# Encoder_pHAT.net
KiCad netlist of a schematic drawn in EAGLE
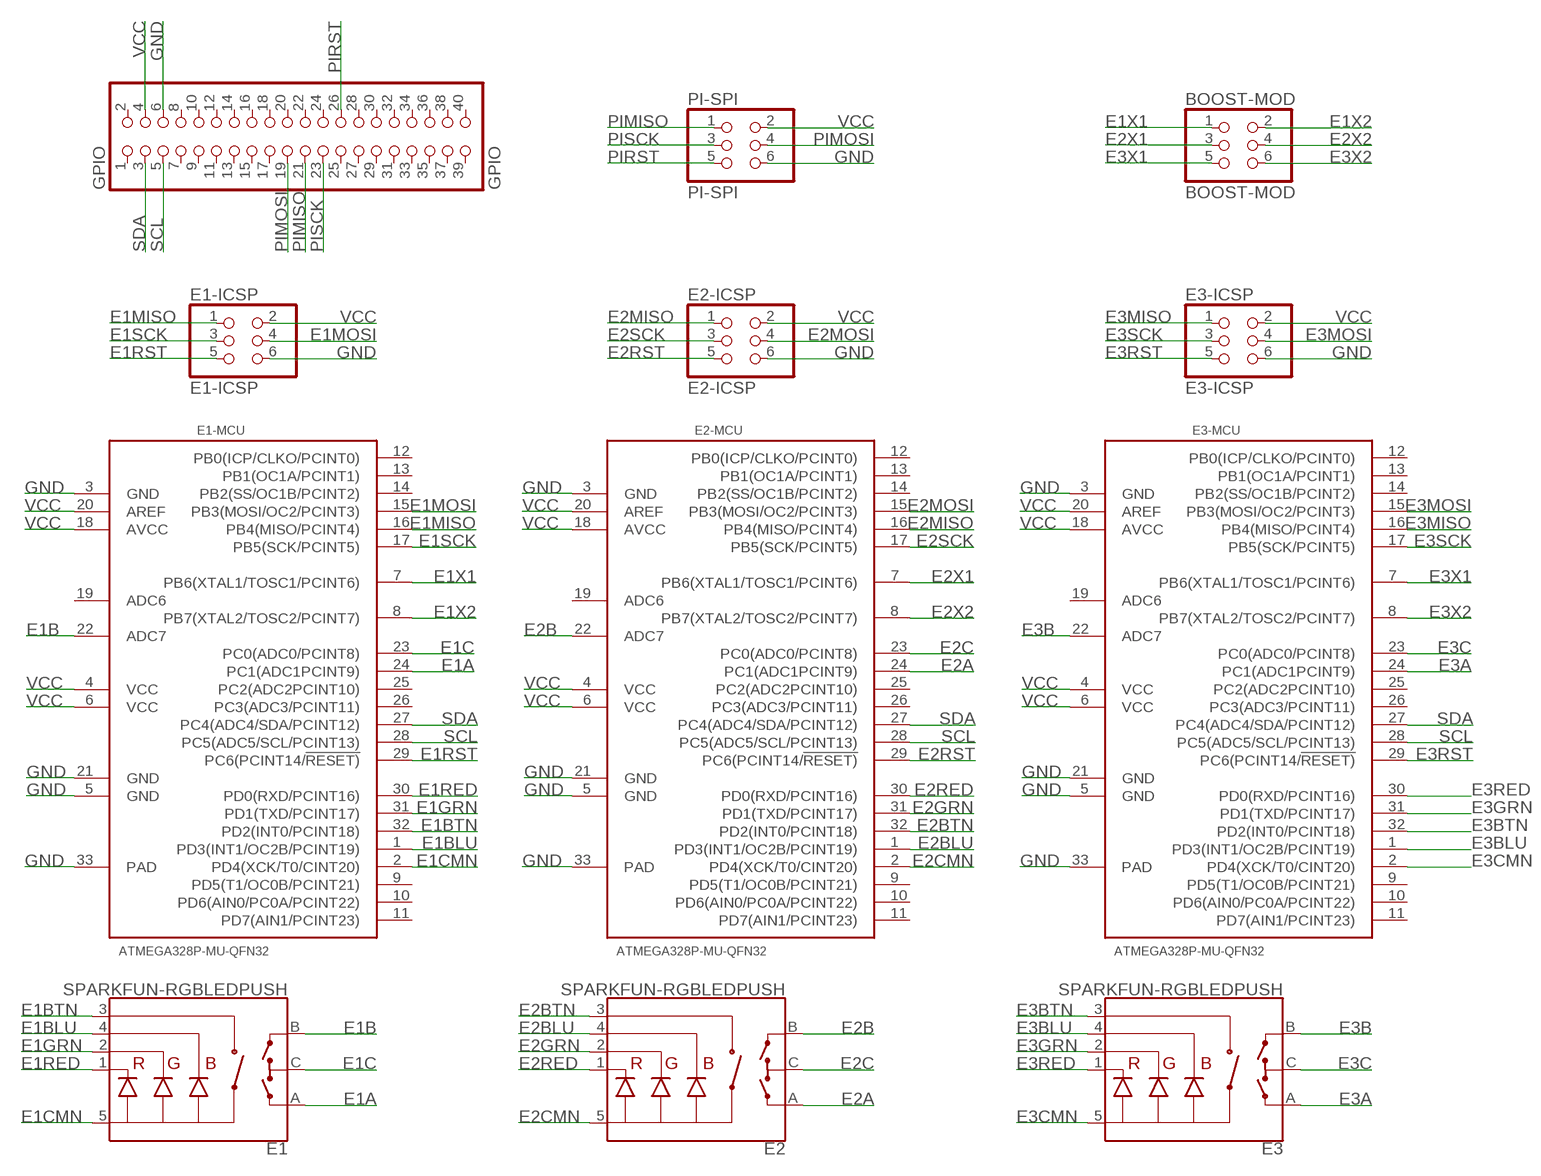
[diagram p0: schematic, sheet 1]

(export (version "E")
  (design (tool "Eeschema 10.0.6"))
  (components
    (comp (ref "BOOST-MOD")
      (value "BOOST-MOD")
      (footprint "eagle-import:2X03")
      (libsource (lib "eagle-import") (part "PINHD-2X3"))
    )
    (comp (ref "E1")
      (value "SPARKFUN-RGBLEDPUSH")
      (footprint "eagle-import:ENCODER_LED_3")
      (libsource (lib "eagle-import") (part "ENCODER-RGB-SWITCH"))
    )
    (comp (ref "E1-ICSP")
      (value "E1-ICSP")
      (footprint "eagle-import:2X03")
      (libsource (lib "eagle-import") (part "PINHD-2X3"))
    )
    (comp (ref "E1-MCU")
      (value "ATMEGA328P-MU-QFN32")
      (footprint "eagle-import:QFN32G-0.5-5X5MM")
      (fields (field (name "MPN") "ATMEGA328P-MU"))
      (libsource (lib "eagle-import") (part "MCU-ATMEGA328P-MU(QFN32)"))
    )
    (comp (ref "E2")
      (value "SPARKFUN-RGBLEDPUSH")
      (footprint "eagle-import:ENCODER_LED_3")
      (libsource (lib "eagle-import") (part "ENCODER-RGB-SWITCH"))
    )
    (comp (ref "E2-ICSP")
      (value "E2-ICSP")
      (footprint "eagle-import:2X03")
      (libsource (lib "eagle-import") (part "PINHD-2X3"))
    )
    (comp (ref "E2-MCU")
      (value "ATMEGA328P-MU-QFN32")
      (footprint "eagle-import:QFN32G-0.5-5X5MM")
      (fields (field (name "MPN") "ATMEGA328P-MU"))
      (libsource (lib "eagle-import") (part "MCU-ATMEGA328P-MU(QFN32)"))
    )
    (comp (ref "E3")
      (value "SPARKFUN-RGBLEDPUSH")
      (footprint "eagle-import:ENCODER_LED_3")
      (libsource (lib "eagle-import") (part "ENCODER-RGB-SWITCH"))
    )
    (comp (ref "E3-ICSP")
      (value "E3-ICSP")
      (footprint "eagle-import:2X03")
      (libsource (lib "eagle-import") (part "PINHD-2X3"))
    )
    (comp (ref "E3-MCU")
      (value "ATMEGA328P-MU-QFN32")
      (footprint "eagle-import:QFN32G-0.5-5X5MM")
      (fields (field (name "MPN") "ATMEGA328P-MU"))
      (libsource (lib "eagle-import") (part "MCU-ATMEGA328P-MU(QFN32)"))
    )
    (comp (ref "GPIO")
      (value "GPIO")
      (footprint "eagle-import:2X20")
      (libsource (lib "eagle-import") (part "PINHD-2X20"))
    )
    (comp (ref "PI-SPI")
      (value "PI-SPI")
      (footprint "eagle-import:2X03")
      (libsource (lib "eagle-import") (part "PINHD-2X3"))
    )
  )
  (nets
    (net (code "1") (name "/E1A") (class "Default")
      (node (ref "E1") (pin "A") (pinfunction "A_A") (pintype "bidirectional"))
      (node (ref "E1-MCU") (pin "24") (pinfunction "PC1(ADC1PCINT9)_24") (pintype "bidirectional"))
    )
    (net (code "2") (name "/E1B") (class "Default")
      (node (ref "E1") (pin "B") (pinfunction "B_B") (pintype "bidirectional"))
      (node (ref "E1-MCU") (pin "22") (pinfunction "ADC7_22") (pintype "bidirectional"))
    )
    (net (code "3") (name "/E1BLU") (class "Default")
      (node (ref "E1") (pin "4") (pinfunction "-B_4") (pintype "passive"))
      (node (ref "E1-MCU") (pin "1") (pinfunction "PD3(INT1/OC2B/PCINT19)_1") (pintype "bidirectional"))
    )
    (net (code "4") (name "/E1BTN") (class "Default")
      (node (ref "E1") (pin "3") (pinfunction "SW_3") (pintype "passive"))
      (node (ref "E1-MCU") (pin "32") (pinfunction "PD2(INT0/PCINT18)_32") (pintype "bidirectional"))
    )
    (net (code "5") (name "/E1C") (class "Default")
      (node (ref "E1") (pin "C") (pinfunction "C_C") (pintype "bidirectional"))
      (node (ref "E1-MCU") (pin "23") (pinfunction "PC0(ADC0/PCINT8)_23") (pintype "bidirectional"))
    )
    (net (code "6") (name "/E1CMN") (class "Default")
      (node (ref "E1") (pin "5") (pinfunction "+_5") (pintype "passive"))
      (node (ref "E1-MCU") (pin "2") (pinfunction "PD4(XCK/T0/CINT20)_2") (pintype "bidirectional"))
    )
    (net (code "7") (name "/E1GRN") (class "Default")
      (node (ref "E1") (pin "2") (pinfunction "-G_2") (pintype "passive"))
      (node (ref "E1-MCU") (pin "31") (pinfunction "PD1(TXD/PCINT17)_31") (pintype "bidirectional"))
    )
    (net (code "8") (name "/E1MISO") (class "Default")
      (node (ref "E1-ICSP") (pin "1") (pinfunction "1_1") (pintype "passive"))
      (node (ref "E1-MCU") (pin "16") (pinfunction "PB4(MISO/PCINT4)_16") (pintype "bidirectional"))
    )
    (net (code "9") (name "/E1MOSI") (class "Default")
      (node (ref "E1-ICSP") (pin "4") (pinfunction "4_4") (pintype "passive"))
      (node (ref "E1-MCU") (pin "15") (pinfunction "PB3(MOSI/OC2/PCINT3)_15") (pintype "bidirectional"))
    )
    (net (code "10") (name "/E1RED") (class "Default")
      (node (ref "E1") (pin "1") (pinfunction "-R_1") (pintype "passive"))
      (node (ref "E1-MCU") (pin "30") (pinfunction "PD0(RXD/PCINT16)_30") (pintype "bidirectional"))
    )
    (net (code "11") (name "/E1RST") (class "Default")
      (node (ref "E1-ICSP") (pin "5") (pinfunction "5_5") (pintype "passive"))
      (node (ref "E1-MCU") (pin "29") (pinfunction "PC6(PCINT14/~{RESET})_29") (pintype "bidirectional"))
    )
    (net (code "12") (name "/E1SCK") (class "Default")
      (node (ref "E1-ICSP") (pin "3") (pinfunction "3_3") (pintype "passive"))
      (node (ref "E1-MCU") (pin "17") (pinfunction "PB5(SCK/PCINT5)_17") (pintype "bidirectional"))
    )
    (net (code "13") (name "/E1X1") (class "Default")
      (node (ref "BOOST-MOD") (pin "1") (pinfunction "1_1") (pintype "passive"))
      (node (ref "E1-MCU") (pin "7") (pinfunction "PB6(XTAL1/TOSC1/PCINT6)_7") (pintype "bidirectional"))
    )
    (net (code "14") (name "/E1X2") (class "Default")
      (node (ref "BOOST-MOD") (pin "2") (pinfunction "2_2") (pintype "passive"))
      (node (ref "E1-MCU") (pin "8") (pinfunction "PB7(XTAL2/TOSC2/PCINT7)_8") (pintype "bidirectional"))
    )
    (net (code "15") (name "/E2A") (class "Default")
      (node (ref "E2") (pin "A") (pinfunction "A_A") (pintype "bidirectional"))
      (node (ref "E2-MCU") (pin "24") (pinfunction "PC1(ADC1PCINT9)_24") (pintype "bidirectional"))
    )
    (net (code "16") (name "/E2B") (class "Default")
      (node (ref "E2") (pin "B") (pinfunction "B_B") (pintype "bidirectional"))
      (node (ref "E2-MCU") (pin "22") (pinfunction "ADC7_22") (pintype "bidirectional"))
    )
    (net (code "17") (name "/E2BLU") (class "Default")
      (node (ref "E2") (pin "4") (pinfunction "-B_4") (pintype "passive"))
      (node (ref "E2-MCU") (pin "1") (pinfunction "PD3(INT1/OC2B/PCINT19)_1") (pintype "bidirectional"))
    )
    (net (code "18") (name "/E2BTN") (class "Default")
      (node (ref "E2") (pin "3") (pinfunction "SW_3") (pintype "passive"))
      (node (ref "E2-MCU") (pin "32") (pinfunction "PD2(INT0/PCINT18)_32") (pintype "bidirectional"))
    )
    (net (code "19") (name "/E2C") (class "Default")
      (node (ref "E2") (pin "C") (pinfunction "C_C") (pintype "bidirectional"))
      (node (ref "E2-MCU") (pin "23") (pinfunction "PC0(ADC0/PCINT8)_23") (pintype "bidirectional"))
    )
    (net (code "20") (name "/E2CMN") (class "Default")
      (node (ref "E2") (pin "5") (pinfunction "+_5") (pintype "passive"))
      (node (ref "E2-MCU") (pin "2") (pinfunction "PD4(XCK/T0/CINT20)_2") (pintype "bidirectional"))
    )
    (net (code "21") (name "/E2GRN") (class "Default")
      (node (ref "E2") (pin "2") (pinfunction "-G_2") (pintype "passive"))
      (node (ref "E2-MCU") (pin "31") (pinfunction "PD1(TXD/PCINT17)_31") (pintype "bidirectional"))
    )
    (net (code "22") (name "/E2MISO") (class "Default")
      (node (ref "E2-ICSP") (pin "1") (pinfunction "1_1") (pintype "passive"))
      (node (ref "E2-MCU") (pin "16") (pinfunction "PB4(MISO/PCINT4)_16") (pintype "bidirectional"))
    )
    (net (code "23") (name "/E2MOSI") (class "Default")
      (node (ref "E2-ICSP") (pin "4") (pinfunction "4_4") (pintype "passive"))
      (node (ref "E2-MCU") (pin "15") (pinfunction "PB3(MOSI/OC2/PCINT3)_15") (pintype "bidirectional"))
    )
    (net (code "24") (name "/E2RED") (class "Default")
      (node (ref "E2") (pin "1") (pinfunction "-R_1") (pintype "passive"))
      (node (ref "E2-MCU") (pin "30") (pinfunction "PD0(RXD/PCINT16)_30") (pintype "bidirectional"))
    )
    (net (code "25") (name "/E2RST") (class "Default")
      (node (ref "E2-ICSP") (pin "5") (pinfunction "5_5") (pintype "passive"))
      (node (ref "E2-MCU") (pin "29") (pinfunction "PC6(PCINT14/~{RESET})_29") (pintype "bidirectional"))
    )
    (net (code "26") (name "/E2SCK") (class "Default")
      (node (ref "E2-ICSP") (pin "3") (pinfunction "3_3") (pintype "passive"))
      (node (ref "E2-MCU") (pin "17") (pinfunction "PB5(SCK/PCINT5)_17") (pintype "bidirectional"))
    )
    (net (code "27") (name "/E2X1") (class "Default")
      (node (ref "BOOST-MOD") (pin "3") (pinfunction "3_3") (pintype "passive"))
      (node (ref "E2-MCU") (pin "7") (pinfunction "PB6(XTAL1/TOSC1/PCINT6)_7") (pintype "bidirectional"))
    )
    (net (code "28") (name "/E2X2") (class "Default")
      (node (ref "BOOST-MOD") (pin "4") (pinfunction "4_4") (pintype "passive"))
      (node (ref "E2-MCU") (pin "8") (pinfunction "PB7(XTAL2/TOSC2/PCINT7)_8") (pintype "bidirectional"))
    )
    (net (code "29") (name "/E3A") (class "Default")
      (node (ref "E3") (pin "A") (pinfunction "A_A") (pintype "bidirectional"))
      (node (ref "E3-MCU") (pin "24") (pinfunction "PC1(ADC1PCINT9)_24") (pintype "bidirectional"))
    )
    (net (code "30") (name "/E3B") (class "Default")
      (node (ref "E3") (pin "B") (pinfunction "B_B") (pintype "bidirectional"))
      (node (ref "E3-MCU") (pin "22") (pinfunction "ADC7_22") (pintype "bidirectional"))
    )
    (net (code "31") (name "/E3BLU") (class "Default")
      (node (ref "E3") (pin "4") (pinfunction "-B_4") (pintype "passive"))
      (node (ref "E3-MCU") (pin "1") (pinfunction "PD3(INT1/OC2B/PCINT19)_1") (pintype "bidirectional"))
    )
    (net (code "32") (name "/E3BTN") (class "Default")
      (node (ref "E3") (pin "3") (pinfunction "SW_3") (pintype "passive"))
      (node (ref "E3-MCU") (pin "32") (pinfunction "PD2(INT0/PCINT18)_32") (pintype "bidirectional"))
    )
    (net (code "33") (name "/E3C") (class "Default")
      (node (ref "E3") (pin "C") (pinfunction "C_C") (pintype "bidirectional"))
      (node (ref "E3-MCU") (pin "23") (pinfunction "PC0(ADC0/PCINT8)_23") (pintype "bidirectional"))
    )
    (net (code "34") (name "/E3CMN") (class "Default")
      (node (ref "E3") (pin "5") (pinfunction "+_5") (pintype "passive"))
      (node (ref "E3-MCU") (pin "2") (pinfunction "PD4(XCK/T0/CINT20)_2") (pintype "bidirectional"))
    )
    (net (code "35") (name "/E3GRN") (class "Default")
      (node (ref "E3") (pin "2") (pinfunction "-G_2") (pintype "passive"))
      (node (ref "E3-MCU") (pin "31") (pinfunction "PD1(TXD/PCINT17)_31") (pintype "bidirectional"))
    )
    (net (code "36") (name "/E3MISO") (class "Default")
      (node (ref "E3-ICSP") (pin "1") (pinfunction "1_1") (pintype "passive"))
      (node (ref "E3-MCU") (pin "16") (pinfunction "PB4(MISO/PCINT4)_16") (pintype "bidirectional"))
    )
    (net (code "37") (name "/E3MOSI") (class "Default")
      (node (ref "E3-ICSP") (pin "4") (pinfunction "4_4") (pintype "passive"))
      (node (ref "E3-MCU") (pin "15") (pinfunction "PB3(MOSI/OC2/PCINT3)_15") (pintype "bidirectional"))
    )
    (net (code "38") (name "/E3RED") (class "Default")
      (node (ref "E3") (pin "1") (pinfunction "-R_1") (pintype "passive"))
      (node (ref "E3-MCU") (pin "30") (pinfunction "PD0(RXD/PCINT16)_30") (pintype "bidirectional"))
    )
    (net (code "39") (name "/E3RST") (class "Default")
      (node (ref "E3-ICSP") (pin "5") (pinfunction "5_5") (pintype "passive"))
      (node (ref "E3-MCU") (pin "29") (pinfunction "PC6(PCINT14/~{RESET})_29") (pintype "bidirectional"))
    )
    (net (code "40") (name "/E3SCK") (class "Default")
      (node (ref "E3-ICSP") (pin "3") (pinfunction "3_3") (pintype "passive"))
      (node (ref "E3-MCU") (pin "17") (pinfunction "PB5(SCK/PCINT5)_17") (pintype "bidirectional"))
    )
    (net (code "41") (name "/E3X1") (class "Default")
      (node (ref "BOOST-MOD") (pin "5") (pinfunction "5_5") (pintype "passive"))
      (node (ref "E3-MCU") (pin "7") (pinfunction "PB6(XTAL1/TOSC1/PCINT6)_7") (pintype "bidirectional"))
    )
    (net (code "42") (name "/E3X2") (class "Default")
      (node (ref "BOOST-MOD") (pin "6") (pinfunction "6_6") (pintype "passive"))
      (node (ref "E3-MCU") (pin "8") (pinfunction "PB7(XTAL2/TOSC2/PCINT7)_8") (pintype "bidirectional"))
    )
    (net (code "43") (name "/GND") (class "Default")
      (node (ref "E1-ICSP") (pin "6") (pinfunction "6_6") (pintype "passive"))
      (node (ref "E1-MCU") (pin "21") (pinfunction "GND_21") (pintype "bidirectional"))
      (node (ref "E1-MCU") (pin "3") (pinfunction "GND_3") (pintype "bidirectional"))
      (node (ref "E1-MCU") (pin "33") (pinfunction "PAD_33") (pintype "bidirectional"))
      (node (ref "E1-MCU") (pin "5") (pinfunction "GND_5") (pintype "bidirectional"))
      (node (ref "E2-ICSP") (pin "6") (pinfunction "6_6") (pintype "passive"))
      (node (ref "E2-MCU") (pin "21") (pinfunction "GND_21") (pintype "bidirectional"))
      (node (ref "E2-MCU") (pin "3") (pinfunction "GND_3") (pintype "bidirectional"))
      (node (ref "E2-MCU") (pin "33") (pinfunction "PAD_33") (pintype "bidirectional"))
      (node (ref "E2-MCU") (pin "5") (pinfunction "GND_5") (pintype "bidirectional"))
      (node (ref "E3-ICSP") (pin "6") (pinfunction "6_6") (pintype "passive"))
      (node (ref "E3-MCU") (pin "21") (pinfunction "GND_21") (pintype "bidirectional"))
      (node (ref "E3-MCU") (pin "3") (pinfunction "GND_3") (pintype "bidirectional"))
      (node (ref "E3-MCU") (pin "33") (pinfunction "PAD_33") (pintype "bidirectional"))
      (node (ref "E3-MCU") (pin "5") (pinfunction "GND_5") (pintype "bidirectional"))
      (node (ref "GPIO") (pin "6") (pinfunction "6_6") (pintype "passive"))
      (node (ref "PI-SPI") (pin "6") (pinfunction "6_6") (pintype "passive"))
    )
    (net (code "44") (name "/PIMISO") (class "Default")
      (node (ref "GPIO") (pin "21") (pinfunction "21_21") (pintype "passive"))
      (node (ref "PI-SPI") (pin "1") (pinfunction "1_1") (pintype "passive"))
    )
    (net (code "45") (name "/PIMOSI") (class "Default")
      (node (ref "GPIO") (pin "19") (pinfunction "19_19") (pintype "passive"))
      (node (ref "PI-SPI") (pin "4") (pinfunction "4_4") (pintype "passive"))
    )
    (net (code "46") (name "/PIRST") (class "Default")
      (node (ref "GPIO") (pin "26") (pinfunction "26_26") (pintype "passive"))
      (node (ref "PI-SPI") (pin "5") (pinfunction "5_5") (pintype "passive"))
    )
    (net (code "47") (name "/PISCK") (class "Default")
      (node (ref "GPIO") (pin "23") (pinfunction "23_23") (pintype "passive"))
      (node (ref "PI-SPI") (pin "3") (pinfunction "3_3") (pintype "passive"))
    )
    (net (code "48") (name "/SCL") (class "Default")
      (node (ref "E1-MCU") (pin "28") (pinfunction "PC5(ADC5/SCL/PCINT13)_28") (pintype "bidirectional"))
      (node (ref "E2-MCU") (pin "28") (pinfunction "PC5(ADC5/SCL/PCINT13)_28") (pintype "bidirectional"))
      (node (ref "E3-MCU") (pin "28") (pinfunction "PC5(ADC5/SCL/PCINT13)_28") (pintype "bidirectional"))
      (node (ref "GPIO") (pin "5") (pinfunction "5_5") (pintype "passive"))
    )
    (net (code "49") (name "/SDA") (class "Default")
      (node (ref "E1-MCU") (pin "27") (pinfunction "PC4(ADC4/SDA/PCINT12)_27") (pintype "bidirectional"))
      (node (ref "E2-MCU") (pin "27") (pinfunction "PC4(ADC4/SDA/PCINT12)_27") (pintype "bidirectional"))
      (node (ref "E3-MCU") (pin "27") (pinfunction "PC4(ADC4/SDA/PCINT12)_27") (pintype "bidirectional"))
      (node (ref "GPIO") (pin "3") (pinfunction "3_3") (pintype "passive"))
    )
    (net (code "50") (name "/VCC") (class "Default")
      (node (ref "E1-ICSP") (pin "2") (pinfunction "2_2") (pintype "passive"))
      (node (ref "E1-MCU") (pin "18") (pinfunction "AVCC_18") (pintype "bidirectional"))
      (node (ref "E1-MCU") (pin "20") (pinfunction "AREF_20") (pintype "bidirectional"))
      (node (ref "E1-MCU") (pin "4") (pinfunction "VCC_4") (pintype "bidirectional"))
      (node (ref "E1-MCU") (pin "6") (pinfunction "VCC_6") (pintype "bidirectional"))
      (node (ref "E2-ICSP") (pin "2") (pinfunction "2_2") (pintype "passive"))
      (node (ref "E2-MCU") (pin "18") (pinfunction "AVCC_18") (pintype "bidirectional"))
      (node (ref "E2-MCU") (pin "20") (pinfunction "AREF_20") (pintype "bidirectional"))
      (node (ref "E2-MCU") (pin "4") (pinfunction "VCC_4") (pintype "bidirectional"))
      (node (ref "E2-MCU") (pin "6") (pinfunction "VCC_6") (pintype "bidirectional"))
      (node (ref "E3-ICSP") (pin "2") (pinfunction "2_2") (pintype "passive"))
      (node (ref "E3-MCU") (pin "18") (pinfunction "AVCC_18") (pintype "bidirectional"))
      (node (ref "E3-MCU") (pin "20") (pinfunction "AREF_20") (pintype "bidirectional"))
      (node (ref "E3-MCU") (pin "4") (pinfunction "VCC_4") (pintype "bidirectional"))
      (node (ref "E3-MCU") (pin "6") (pinfunction "VCC_6") (pintype "bidirectional"))
      (node (ref "GPIO") (pin "4") (pinfunction "4_4") (pintype "passive"))
      (node (ref "PI-SPI") (pin "2") (pinfunction "2_2") (pintype "passive"))
    )
    (net (code "51") (name "unconnected-(E1-MCU-ADC6-Pad19)") (class "Default")
      (node (ref "E1-MCU") (pin "19") (pinfunction "ADC6_19") (pintype "bidirectional"))
    )
    (net (code "52") (name "unconnected-(E1-MCU-PB0(ICP{slash}CLKO{slash}PCINT0)-Pad12)") (class "Default")
      (node (ref "E1-MCU") (pin "12") (pinfunction "PB0(ICP/CLKO/PCINT0)_12") (pintype "bidirectional"))
    )
    (net (code "53") (name "unconnected-(E1-MCU-PB1(OC1A{slash}PCINT1)-Pad13)") (class "Default")
      (node (ref "E1-MCU") (pin "13") (pinfunction "PB1(OC1A/PCINT1)_13") (pintype "bidirectional"))
    )
    (net (code "54") (name "unconnected-(E1-MCU-PB2(SS{slash}OC1B{slash}PCINT2)-Pad14)") (class "Default")
      (node (ref "E1-MCU") (pin "14") (pinfunction "PB2(SS/OC1B/PCINT2)_14") (pintype "bidirectional"))
    )
    (net (code "55") (name "unconnected-(E1-MCU-PC2(ADC2PCINT10)-Pad25)") (class "Default")
      (node (ref "E1-MCU") (pin "25") (pinfunction "PC2(ADC2PCINT10)_25") (pintype "bidirectional"))
    )
    (net (code "56") (name "unconnected-(E1-MCU-PC3(ADC3{slash}PCINT11)-Pad26)") (class "Default")
      (node (ref "E1-MCU") (pin "26") (pinfunction "PC3(ADC3/PCINT11)_26") (pintype "bidirectional"))
    )
    (net (code "57") (name "unconnected-(E1-MCU-PD5(T1{slash}OC0B{slash}PCINT21)-Pad9)") (class "Default")
      (node (ref "E1-MCU") (pin "9") (pinfunction "PD5(T1/OC0B/PCINT21)_9") (pintype "bidirectional"))
    )
    (net (code "58") (name "unconnected-(E1-MCU-PD6(AIN0{slash}PC0A{slash}PCINT22)-Pad10)") (class "Default")
      (node (ref "E1-MCU") (pin "10") (pinfunction "PD6(AIN0/PC0A/PCINT22)_10") (pintype "bidirectional"))
    )
    (net (code "59") (name "unconnected-(E1-MCU-PD7(AIN1{slash}PCINT23)-Pad11)") (class "Default")
      (node (ref "E1-MCU") (pin "11") (pinfunction "PD7(AIN1/PCINT23)_11") (pintype "bidirectional"))
    )
    (net (code "60") (name "unconnected-(E2-MCU-ADC6-Pad19)") (class "Default")
      (node (ref "E2-MCU") (pin "19") (pinfunction "ADC6_19") (pintype "bidirectional"))
    )
    (net (code "61") (name "unconnected-(E2-MCU-PB0(ICP{slash}CLKO{slash}PCINT0)-Pad12)") (class "Default")
      (node (ref "E2-MCU") (pin "12") (pinfunction "PB0(ICP/CLKO/PCINT0)_12") (pintype "bidirectional"))
    )
    (net (code "62") (name "unconnected-(E2-MCU-PB1(OC1A{slash}PCINT1)-Pad13)") (class "Default")
      (node (ref "E2-MCU") (pin "13") (pinfunction "PB1(OC1A/PCINT1)_13") (pintype "bidirectional"))
    )
    (net (code "63") (name "unconnected-(E2-MCU-PB2(SS{slash}OC1B{slash}PCINT2)-Pad14)") (class "Default")
      (node (ref "E2-MCU") (pin "14") (pinfunction "PB2(SS/OC1B/PCINT2)_14") (pintype "bidirectional"))
    )
    (net (code "64") (name "unconnected-(E2-MCU-PC2(ADC2PCINT10)-Pad25)") (class "Default")
      (node (ref "E2-MCU") (pin "25") (pinfunction "PC2(ADC2PCINT10)_25") (pintype "bidirectional"))
    )
    (net (code "65") (name "unconnected-(E2-MCU-PC3(ADC3{slash}PCINT11)-Pad26)") (class "Default")
      (node (ref "E2-MCU") (pin "26") (pinfunction "PC3(ADC3/PCINT11)_26") (pintype "bidirectional"))
    )
    (net (code "66") (name "unconnected-(E2-MCU-PD5(T1{slash}OC0B{slash}PCINT21)-Pad9)") (class "Default")
      (node (ref "E2-MCU") (pin "9") (pinfunction "PD5(T1/OC0B/PCINT21)_9") (pintype "bidirectional"))
    )
    (net (code "67") (name "unconnected-(E2-MCU-PD6(AIN0{slash}PC0A{slash}PCINT22)-Pad10)") (class "Default")
      (node (ref "E2-MCU") (pin "10") (pinfunction "PD6(AIN0/PC0A/PCINT22)_10") (pintype "bidirectional"))
    )
    (net (code "68") (name "unconnected-(E2-MCU-PD7(AIN1{slash}PCINT23)-Pad11)") (class "Default")
      (node (ref "E2-MCU") (pin "11") (pinfunction "PD7(AIN1/PCINT23)_11") (pintype "bidirectional"))
    )
    (net (code "69") (name "unconnected-(E3-MCU-ADC6-Pad19)") (class "Default")
      (node (ref "E3-MCU") (pin "19") (pinfunction "ADC6_19") (pintype "bidirectional"))
    )
    (net (code "70") (name "unconnected-(E3-MCU-PB0(ICP{slash}CLKO{slash}PCINT0)-Pad12)") (class "Default")
      (node (ref "E3-MCU") (pin "12") (pinfunction "PB0(ICP/CLKO/PCINT0)_12") (pintype "bidirectional"))
    )
    (net (code "71") (name "unconnected-(E3-MCU-PB1(OC1A{slash}PCINT1)-Pad13)") (class "Default")
      (node (ref "E3-MCU") (pin "13") (pinfunction "PB1(OC1A/PCINT1)_13") (pintype "bidirectional"))
    )
    (net (code "72") (name "unconnected-(E3-MCU-PB2(SS{slash}OC1B{slash}PCINT2)-Pad14)") (class "Default")
      (node (ref "E3-MCU") (pin "14") (pinfunction "PB2(SS/OC1B/PCINT2)_14") (pintype "bidirectional"))
    )
    (net (code "73") (name "unconnected-(E3-MCU-PC2(ADC2PCINT10)-Pad25)") (class "Default")
      (node (ref "E3-MCU") (pin "25") (pinfunction "PC2(ADC2PCINT10)_25") (pintype "bidirectional"))
    )
    (net (code "74") (name "unconnected-(E3-MCU-PC3(ADC3{slash}PCINT11)-Pad26)") (class "Default")
      (node (ref "E3-MCU") (pin "26") (pinfunction "PC3(ADC3/PCINT11)_26") (pintype "bidirectional"))
    )
    (net (code "75") (name "unconnected-(E3-MCU-PD5(T1{slash}OC0B{slash}PCINT21)-Pad9)") (class "Default")
      (node (ref "E3-MCU") (pin "9") (pinfunction "PD5(T1/OC0B/PCINT21)_9") (pintype "bidirectional"))
    )
    (net (code "76") (name "unconnected-(E3-MCU-PD6(AIN0{slash}PC0A{slash}PCINT22)-Pad10)") (class "Default")
      (node (ref "E3-MCU") (pin "10") (pinfunction "PD6(AIN0/PC0A/PCINT22)_10") (pintype "bidirectional"))
    )
    (net (code "77") (name "unconnected-(E3-MCU-PD7(AIN1{slash}PCINT23)-Pad11)") (class "Default")
      (node (ref "E3-MCU") (pin "11") (pinfunction "PD7(AIN1/PCINT23)_11") (pintype "bidirectional"))
    )
    (net (code "78") (name "unconnected-(GPIO-Pad1)") (class "Default")
      (node (ref "GPIO") (pin "1") (pinfunction "1_1") (pintype "passive"))
    )
    (net (code "79") (name "unconnected-(GPIO-Pad2)") (class "Default")
      (node (ref "GPIO") (pin "2") (pinfunction "2_2") (pintype "passive"))
    )
    (net (code "80") (name "unconnected-(GPIO-Pad7)") (class "Default")
      (node (ref "GPIO") (pin "7") (pinfunction "7_7") (pintype "passive"))
    )
    (net (code "81") (name "unconnected-(GPIO-Pad8)") (class "Default")
      (node (ref "GPIO") (pin "8") (pinfunction "8_8") (pintype "passive"))
    )
    (net (code "82") (name "unconnected-(GPIO-Pad9)") (class "Default")
      (node (ref "GPIO") (pin "9") (pinfunction "9_9") (pintype "passive"))
    )
    (net (code "83") (name "unconnected-(GPIO-Pad10)") (class "Default")
      (node (ref "GPIO") (pin "10") (pinfunction "10_10") (pintype "passive"))
    )
    (net (code "84") (name "unconnected-(GPIO-Pad11)") (class "Default")
      (node (ref "GPIO") (pin "11") (pinfunction "11_11") (pintype "passive"))
    )
    (net (code "85") (name "unconnected-(GPIO-Pad12)") (class "Default")
      (node (ref "GPIO") (pin "12") (pinfunction "12_12") (pintype "passive"))
    )
    (net (code "86") (name "unconnected-(GPIO-Pad13)") (class "Default")
      (node (ref "GPIO") (pin "13") (pinfunction "13_13") (pintype "passive"))
    )
    (net (code "87") (name "unconnected-(GPIO-Pad14)") (class "Default")
      (node (ref "GPIO") (pin "14") (pinfunction "14_14") (pintype "passive"))
    )
    (net (code "88") (name "unconnected-(GPIO-Pad15)") (class "Default")
      (node (ref "GPIO") (pin "15") (pinfunction "15_15") (pintype "passive"))
    )
    (net (code "89") (name "unconnected-(GPIO-Pad16)") (class "Default")
      (node (ref "GPIO") (pin "16") (pinfunction "16_16") (pintype "passive"))
    )
    (net (code "90") (name "unconnected-(GPIO-Pad17)") (class "Default")
      (node (ref "GPIO") (pin "17") (pinfunction "17_17") (pintype "passive"))
    )
    (net (code "91") (name "unconnected-(GPIO-Pad18)") (class "Default")
      (node (ref "GPIO") (pin "18") (pinfunction "18_18") (pintype "passive"))
    )
    (net (code "92") (name "unconnected-(GPIO-Pad20)") (class "Default")
      (node (ref "GPIO") (pin "20") (pinfunction "20_20") (pintype "passive"))
    )
    (net (code "93") (name "unconnected-(GPIO-Pad22)") (class "Default")
      (node (ref "GPIO") (pin "22") (pinfunction "22_22") (pintype "passive"))
    )
    (net (code "94") (name "unconnected-(GPIO-Pad24)") (class "Default")
      (node (ref "GPIO") (pin "24") (pinfunction "24_24") (pintype "passive"))
    )
    (net (code "95") (name "unconnected-(GPIO-Pad25)") (class "Default")
      (node (ref "GPIO") (pin "25") (pinfunction "25_25") (pintype "passive"))
    )
    (net (code "96") (name "unconnected-(GPIO-Pad27)") (class "Default")
      (node (ref "GPIO") (pin "27") (pinfunction "27_27") (pintype "passive"))
    )
    (net (code "97") (name "unconnected-(GPIO-Pad28)") (class "Default")
      (node (ref "GPIO") (pin "28") (pinfunction "28_28") (pintype "passive"))
    )
    (net (code "98") (name "unconnected-(GPIO-Pad29)") (class "Default")
      (node (ref "GPIO") (pin "29") (pinfunction "29_29") (pintype "passive"))
    )
    (net (code "99") (name "unconnected-(GPIO-Pad30)") (class "Default")
      (node (ref "GPIO") (pin "30") (pinfunction "30_30") (pintype "passive"))
    )
    (net (code "100") (name "unconnected-(GPIO-Pad31)") (class "Default")
      (node (ref "GPIO") (pin "31") (pinfunction "31_31") (pintype "passive"))
    )
    (net (code "101") (name "unconnected-(GPIO-Pad32)") (class "Default")
      (node (ref "GPIO") (pin "32") (pinfunction "32_32") (pintype "passive"))
    )
    (net (code "102") (name "unconnected-(GPIO-Pad33)") (class "Default")
      (node (ref "GPIO") (pin "33") (pinfunction "33_33") (pintype "passive"))
    )
    (net (code "103") (name "unconnected-(GPIO-Pad34)") (class "Default")
      (node (ref "GPIO") (pin "34") (pinfunction "34_34") (pintype "passive"))
    )
    (net (code "104") (name "unconnected-(GPIO-Pad35)") (class "Default")
      (node (ref "GPIO") (pin "35") (pinfunction "35_35") (pintype "passive"))
    )
    (net (code "105") (name "unconnected-(GPIO-Pad36)") (class "Default")
      (node (ref "GPIO") (pin "36") (pinfunction "36_36") (pintype "passive"))
    )
    (net (code "106") (name "unconnected-(GPIO-Pad37)") (class "Default")
      (node (ref "GPIO") (pin "37") (pinfunction "37_37") (pintype "passive"))
    )
    (net (code "107") (name "unconnected-(GPIO-Pad38)") (class "Default")
      (node (ref "GPIO") (pin "38") (pinfunction "38_38") (pintype "passive"))
    )
    (net (code "108") (name "unconnected-(GPIO-Pad39)") (class "Default")
      (node (ref "GPIO") (pin "39") (pinfunction "39_39") (pintype "passive"))
    )
    (net (code "109") (name "unconnected-(GPIO-Pad40)") (class "Default")
      (node (ref "GPIO") (pin "40") (pinfunction "40_40") (pintype "passive"))
    )
  )
)
